# dcf77kompZDiff.net
KiCad netlist of a schematic drawn in EAGLE
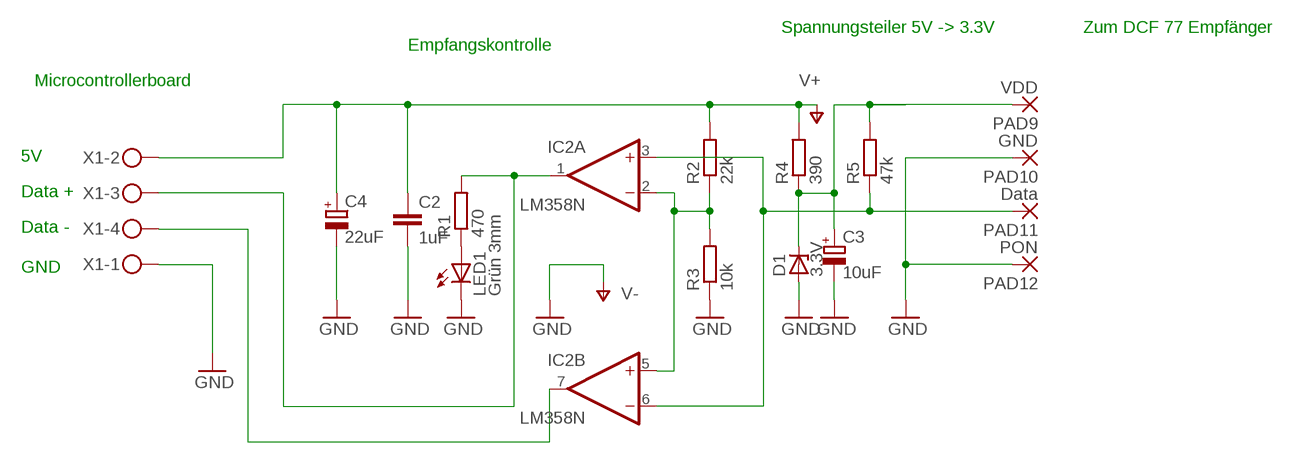
[diagram p0: schematic, sheet 1]

(export (version "E")
  (design (tool "Eeschema 10.0.6"))
  (components
    (comp (ref "C2")
      (value "1uF")
      (footprint "eagle-import:C050-050X075")
      (libsource (lib "eagle-import") (part "C-EU050-050X075"))
    )
    (comp (ref "C3")
      (value "10uF")
      (footprint "eagle-import:E2,5-5")
      (libsource (lib "eagle-import") (part "CPOL-EUE2.5-5"))
    )
    (comp (ref "C4")
      (value "22uF")
      (footprint "eagle-import:E5-10,5")
      (libsource (lib "eagle-import") (part "resistor_CPOL-EUE5-10.5"))
    )
    (comp (ref "D1")
      (value "3.3V")
      (footprint "eagle-import:DO34Z7")
      (libsource (lib "eagle-import") (part "ZENER-DIODEDO34-7"))
    )
    (comp (ref "IC2")
      (value "LM358N")
      (footprint "eagle-import:DIL08")
      (libsource (lib "eagle-import") (part "LM358N"))
    )
    (comp (ref "LED1")
      (value "Grün 3mm")
      (footprint "eagle-import:LED5MM")
      (libsource (lib "eagle-import") (part "LED5MM"))
    )
    (comp (ref "PAD9")
      (value "VDD")
      (footprint "eagle-import:1,6_0,9")
      (libsource (lib "eagle-import") (part "1,6/0,9"))
    )
    (comp (ref "PAD10")
      (value "GND")
      (footprint "eagle-import:1,6_0,9")
      (libsource (lib "eagle-import") (part "1,6/0,9"))
    )
    (comp (ref "PAD11")
      (value "Data")
      (footprint "eagle-import:1,6_0,9")
      (libsource (lib "eagle-import") (part "1,6/0,9"))
    )
    (comp (ref "PAD12")
      (value "PON")
      (footprint "eagle-import:1,6_0,9")
      (libsource (lib "eagle-import") (part "1,6/0,9"))
    )
    (comp (ref "R1")
      (value "470")
      (footprint "eagle-import:0207_10")
      (libsource (lib "eagle-import") (part "R-EU_0207/10"))
    )
    (comp (ref "R2")
      (value "22k")
      (footprint "eagle-import:0207_10")
      (libsource (lib "eagle-import") (part "R-EU_0207/10"))
    )
    (comp (ref "R3")
      (value "10k")
      (footprint "eagle-import:0207_10")
      (libsource (lib "eagle-import") (part "R-EU_0207/10"))
    )
    (comp (ref "R4")
      (value "390")
      (footprint "eagle-import:0207_10")
      (libsource (lib "eagle-import") (part "R-EU_0207/10"))
    )
    (comp (ref "R5")
      (value "47k")
      (footprint "eagle-import:0207_10")
      (libsource (lib "eagle-import") (part "R-EU_0207/10"))
    )
    (comp (ref "X1")
      (value "MKDSN1,5/4-5,08")
      (footprint "eagle-import:MKDSN1,5_4-5,08")
      (fields (field (name "MPN") "SMKDSN1,5/4-5,08"))
      (libsource (lib "eagle-import") (part "MKDSN1,5/4-5,08"))
    )
  )
  (nets
    (net (code "1") (name "GND") (class "Default")
      (node (ref "C2") (pin "2") (pinfunction "2_2") (pintype "passive"))
      (node (ref "C3") (pin "-") (pinfunction "-_-") (pintype "passive"))
      (node (ref "C4") (pin "-") (pinfunction "-_-") (pintype "passive"))
      (node (ref "D1") (pin "A") (pinfunction "A_A") (pintype "passive"))
      (node (ref "LED1") (pin "K") (pinfunction "C_K") (pintype "passive"))
      (node (ref "PAD10") (pin "1") (pinfunction "P_1") (pintype "passive"))
      (node (ref "PAD12") (pin "1") (pinfunction "P_1") (pintype "passive"))
      (node (ref "R3") (pin "1") (pinfunction "1_1") (pintype "passive"))
      (node (ref "X1") (pin "1") (pinfunction "KL_1") (pintype "passive"))
    )
    (net (code "2") (name "Net-(IC2A-+IN)") (class "Default")
      (node (ref "IC2") (pin "3") (pinfunction "+IN_3") (pintype "input"))
      (node (ref "IC2") (pin "6") (pinfunction "-IN_6") (pintype "input"))
      (node (ref "PAD11") (pin "1") (pinfunction "P_1") (pintype "passive"))
      (node (ref "R5") (pin "1") (pinfunction "1_1") (pintype "passive"))
    )
    (net (code "3") (name "Net-(IC2A--IN)") (class "Default")
      (node (ref "IC2") (pin "2") (pinfunction "-IN_2") (pintype "input"))
      (node (ref "IC2") (pin "5") (pinfunction "+IN_5") (pintype "input"))
      (node (ref "R2") (pin "1") (pinfunction "1_1") (pintype "passive"))
      (node (ref "R3") (pin "2") (pinfunction "2_2") (pintype "passive"))
    )
    (net (code "4") (name "Net-(IC2A-OUT)") (class "Default")
      (node (ref "IC2") (pin "1") (pinfunction "OUT_1") (pintype "output"))
      (node (ref "R1") (pin "2") (pinfunction "2_2") (pintype "passive"))
      (node (ref "X1") (pin "3") (pinfunction "KL_3") (pintype "passive"))
    )
    (net (code "5") (name "Net-(IC2B-OUT)") (class "Default")
      (node (ref "IC2") (pin "7") (pinfunction "OUT_7") (pintype "output"))
      (node (ref "X1") (pin "4") (pinfunction "KL_4") (pintype "passive"))
    )
    (net (code "6") (name "Net-(LED1-PadA)") (class "Default")
      (node (ref "LED1") (pin "A") (pinfunction "A_A") (pintype "passive"))
      (node (ref "R1") (pin "1") (pinfunction "1_1") (pintype "passive"))
    )
    (net (code "7") (name "Net-(PAD9-P)") (class "Default")
      (node (ref "C3") (pin "+") (pinfunction "+_+") (pintype "passive"))
      (node (ref "D1") (pin "C") (pinfunction "C_C") (pintype "passive"))
      (node (ref "PAD9") (pin "1") (pinfunction "P_1") (pintype "passive"))
      (node (ref "R4") (pin "1") (pinfunction "1_1") (pintype "passive"))
      (node (ref "R5") (pin "2") (pinfunction "2_2") (pintype "passive"))
    )
    (net (code "8") (name "V+") (class "Default")
      (node (ref "C2") (pin "1") (pinfunction "1_1") (pintype "passive"))
      (node (ref "C4") (pin "+") (pinfunction "+_+") (pintype "passive"))
      (node (ref "R2") (pin "2") (pinfunction "2_2") (pintype "passive"))
      (node (ref "R4") (pin "2") (pinfunction "2_2") (pintype "passive"))
      (node (ref "X1") (pin "2") (pinfunction "KL_2") (pintype "passive"))
    )
  )
)
